# BATTERY.net
KiCad netlist of a schematic drawn in Altium Designer
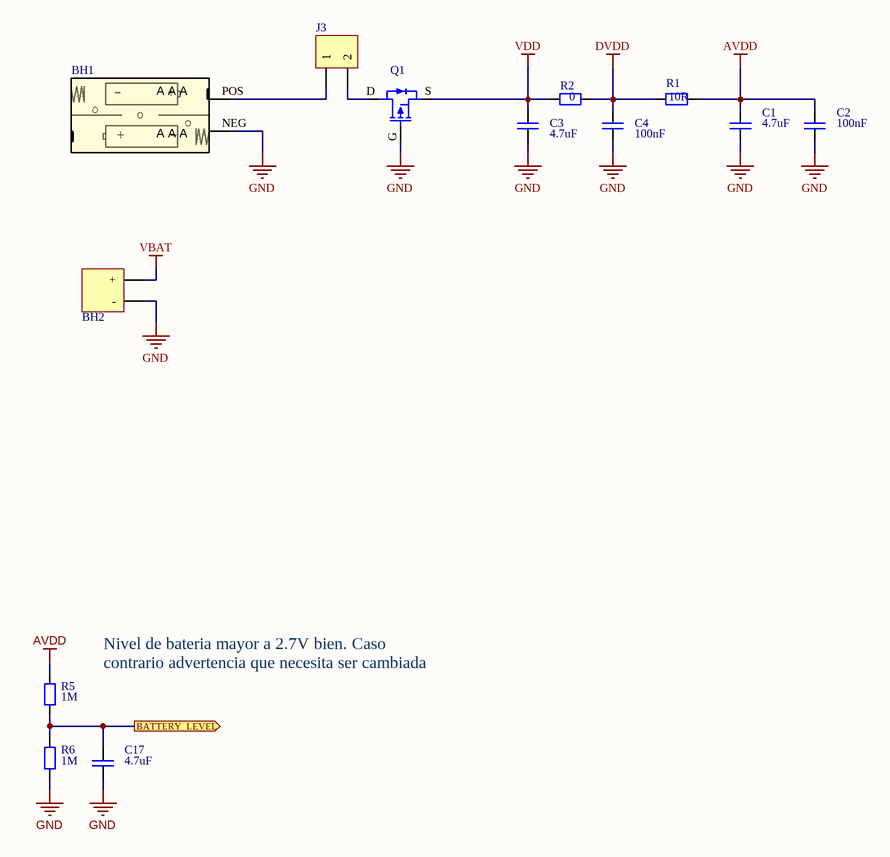
[diagram p0: BATTERY.SchDoc]

(export (version "E")
  (design (tool "Eeschema 10.0.6"))
  (components
    (comp (ref "BH1")
      (value "2468")
      (footprint "BATTERY_HOLDER_2XAAA")
      (description "2 x AAA through hole economic type")
      (fields (field (name "MANUFACTURER") "Keystone Electronics"))
      (libsource (lib "Battery_Holders") (part "2468"))
    )
    (comp (ref "BH2")
      (value "Battery Holder CR2032")
      (footprint "BS-08-B2AA016")
      (description "Battery base -25℃~+85℃ CR2032 SMD Battery Connectors ROHS")
      (fields
        (field (name "MANUFACTURER") "Myoung")
        (field (name "MANUFACTURER PART NUMBER") "BS-08-B2AA016")
      )
      (libsource (lib "Battery_Holders") (part "BS-08-B2AA016"))
    )
    (comp (ref "C1")
      (value "4.7uF")
      (footprint "CAP_SM0805_YAGEOCC2_N")
      (description "CAP 4.7uF SM0805 X5R 10V YAGEO CC2")
      (fields
        (field (name "MANUFACTURER") "Yageo")
        (field (name "MANUFACTURER PART NUMBER") "CC0805KRX5R6BB475")
      )
      (libsource (lib "Yageo") (part "CC0805KRX5R6BB475"))
    )
    (comp (ref "C2")
      (value "100nF")
      (footprint "CAP_SM0805_YAGEOCC2_N")
      (description "CAP 100nF SM0805 X7R 25V YAGEO CC2")
      (fields
        (field (name "MANUFACTURER") "Yageo")
        (field (name "MANUFACTURER PART NUMBER") "CC0805KRX7R8BB104")
      )
      (libsource (lib "Yageo") (part "CC0805KRX7R8BB104"))
    )
    (comp (ref "C3")
      (value "4.7uF")
      (footprint "CAP_SM0805_YAGEOCC2_N")
      (description "CAP 4.7uF SM0805 X5R 10V YAGEO CC2")
      (fields
        (field (name "MANUFACTURER") "Yageo")
        (field (name "MANUFACTURER PART NUMBER") "CC0805KRX5R6BB475")
      )
      (libsource (lib "Yageo") (part "CC0805KRX5R6BB475"))
    )
    (comp (ref "C4")
      (value "100nF")
      (footprint "CAP_SM0805_YAGEOCC2_N")
      (description "CAP 100nF SM0805 X7R 25V YAGEO CC2")
      (fields
        (field (name "MANUFACTURER") "Yageo")
        (field (name "MANUFACTURER PART NUMBER") "CC0805KRX7R8BB104")
      )
      (libsource (lib "Yageo") (part "CC0805KRX7R8BB104"))
    )
    (comp (ref "C17")
      (value "4.7uF")
      (footprint "CAP_SM0805_YAGEOCC2_N")
      (description "CAP 4.7uF SM0805 X5R 10V YAGEO CC2")
      (fields
        (field (name "MANUFACTURER") "Yageo")
        (field (name "MANUFACTURER PART NUMBER") "CC0805KRX5R6BB475")
      )
      (libsource (lib "Yageo") (part "CC0805KRX5R6BB475"))
    )
    (comp (ref "J3")
      (value "Usar Equivalente")
      (footprint "HEADER PIN 1X2")
      (description "1 x 2 - true hole  2.54mm - Pb free")
      (fields
        (field (name "MANUFACTURER") "Amphenol ICC")
        (field (name "MANUFACTURER PART NUMBER") "54101-T0602LF")
      )
      (libsource (lib "header_pin") (part "54101-T0602LF"))
    )
    (comp (ref "Q1")
      (value "DMG3401LSN-7")
      (footprint "DMG3401LSN-7")
      (description "P-CHANNEL ENHANCEMENT MODE MOSFET\r\nRDS(ON) = 85mΩ @ VGS = -2.5V -> ID -2.7A\r\nV(BR)DDS 30V")
      (fields (field (name "MANUFACTURER") "Diodes Incorporated"))
      (libsource (lib "mosfet") (part "DMG3401LSN-7"))
    )
    (comp (ref "R1")
      (value "10R")
      (footprint "RES_SM0805_YAGEORC_N")
      (description "RES 10R SM0805 YAGEO RC_L")
      (fields
        (field (name "MANUFACTURER") "Yageo")
        (field (name "MANUFACTURER PART NUMBER") "RC0805FR-0710RL")
      )
      (libsource (lib "Yageo") (part "RC0805FR-0710RL"))
    )
    (comp (ref "R2")
      (value "0")
      (footprint "RES_SM0805_YAGEORC_N")
      (description "RES 0 OHMS SM0805 YAGEO RC_L")
      (fields
        (field (name "MANUFACTURER") "Yageo")
        (field (name "MANUFACTURER PART NUMBER") "RC0603FR-070RL")
      )
      (libsource (lib "Yageo") (part "RC0805JR-070RL"))
    )
    (comp (ref "R5")
      (value "1M")
      (footprint "RES_SM0805_YAGEORC_N")
      (description "RES 1M SM0805 YAGEO RC_L")
      (fields
        (field (name "MANUFACTURER") "Yageo")
        (field (name "MANUFACTURER PART NUMBER") "RC0805FR-071ML")
      )
      (libsource (lib "Yageo") (part "RC0805FR-071ML"))
    )
    (comp (ref "R6")
      (value "1M")
      (footprint "RES_SM0805_YAGEORC_N")
      (description "RES 1M SM0805 YAGEO RC_L")
      (fields
        (field (name "MANUFACTURER") "Yageo")
        (field (name "MANUFACTURER PART NUMBER") "RC0805FR-071ML")
      )
      (libsource (lib "Yageo") (part "RC0805FR-071ML"))
    )
  )
  (nets
    (net (code "1") (name "/BATTERY_LEVEL") (class "Default")
      (node (ref "C17") (pin "1") (pintype "passive"))
      (node (ref "R5") (pin "1") (pintype "passive"))
      (node (ref "R6") (pin "2") (pintype "passive"))
    )
    (net (code "2") (name "AVDD") (class "Default")
      (node (ref "C1") (pin "1") (pintype "passive"))
      (node (ref "C2") (pin "1") (pintype "passive"))
      (node (ref "R1") (pin "2") (pintype "passive"))
      (node (ref "R5") (pin "2") (pintype "passive"))
    )
    (net (code "3") (name "DVDD") (class "Default")
      (node (ref "C4") (pin "1") (pintype "passive"))
      (node (ref "R1") (pin "1") (pintype "passive"))
      (node (ref "R2") (pin "2") (pintype "passive"))
    )
    (net (code "4") (name "GND") (class "Default")
      (node (ref "BH1") (pin "NEG") (pinfunction "NEG_NEG") (pintype "passive"))
      (node (ref "BH2") (pin "NEG") (pinfunction "-_NEG") (pintype "passive"))
      (node (ref "C1") (pin "2") (pintype "passive"))
      (node (ref "C17") (pin "2") (pintype "passive"))
      (node (ref "C2") (pin "2") (pintype "passive"))
      (node (ref "C3") (pin "2") (pintype "passive"))
      (node (ref "C4") (pin "2") (pintype "passive"))
      (node (ref "Q1") (pin "G") (pinfunction "G_G") (pintype "passive"))
      (node (ref "R6") (pin "1") (pintype "passive"))
    )
    (net (code "5") (name "Net-(BH1-PadPOS)") (class "Default")
      (node (ref "BH1") (pin "POS") (pinfunction "POS_POS") (pintype "passive"))
      (node (ref "J3") (pin "1") (pinfunction "1_1") (pintype "passive"))
    )
    (net (code "6") (name "Net-(J3-Pad2)") (class "Default")
      (node (ref "J3") (pin "2") (pinfunction "2_2") (pintype "passive"))
      (node (ref "Q1") (pin "D") (pinfunction "D_D") (pintype "passive"))
    )
    (net (code "7") (name "VBAT") (class "Default")
      (node (ref "BH2") (pin "POS") (pinfunction "+_POS") (pintype "passive"))
    )
    (net (code "8") (name "VDD") (class "Default")
      (node (ref "C3") (pin "1") (pintype "passive"))
      (node (ref "Q1") (pin "S") (pinfunction "S_S") (pintype "passive"))
      (node (ref "R2") (pin "1") (pintype "passive"))
    )
  )
)
